# etna-sch-pmic.net
KiCad netlist of a schematic drawn in Altium Designer
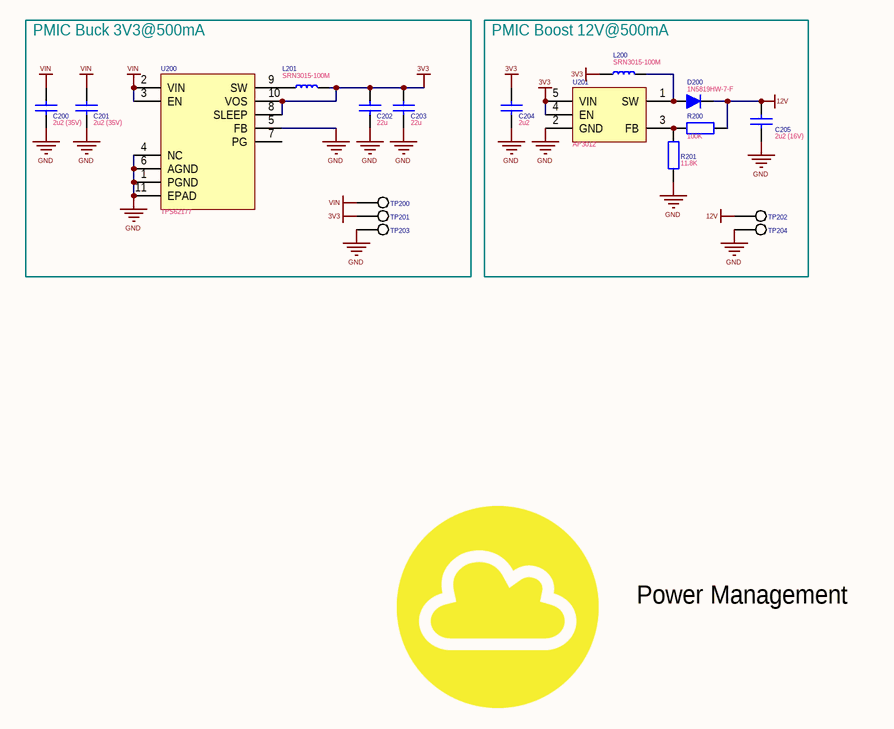
[diagram p0: etna-sch-pmic.SchDoc]

(export (version "E")
  (design (tool "Eeschema 10.0.6"))
  (components
    (comp (ref "C200")
      (value "2u2 (35V)")
      (footprint "0805-CAP")
      (description "Capacitor")
      (libsource (lib "illysky-components") (part "CAP"))
    )
    (comp (ref "C201")
      (value "2u2 (35V)")
      (footprint "0805-CAP")
      (description "Capacitor")
      (libsource (lib "illysky-components") (part "CAP"))
    )
    (comp (ref "C202")
      (value "22u")
      (footprint "0805-CAP")
      (description "Capacitor")
      (libsource (lib "illysky-components") (part "CAP"))
    )
    (comp (ref "C203")
      (value "22u")
      (footprint "0805-CAP")
      (description "Capacitor")
      (libsource (lib "illysky-components") (part "CAP"))
    )
    (comp (ref "C204")
      (value "2u2")
      (footprint "0603-capacitor")
      (description "Capacitor")
      (libsource (lib "illysky-components") (part "CAP"))
    )
    (comp (ref "C205")
      (value "2u2 (16V)")
      (footprint "0603-capacitor")
      (description "Capacitor")
      (libsource (lib "illysky-components") (part "CAP"))
    )
    (comp (ref "D200")
      (value "1N5819HW-7-F")
      (footprint "SOD123-DIODE")
      (description "Diode")
      (fields (field (name "PUBLISHER") "Altium Limited"))
      (libsource (lib "illysky-components") (part "DIODE"))
    )
    (comp (ref "L200")
      (value "SRN3015-100M")
      (footprint "SRN3015")
      (description "Inductor or Ferrite")
      (libsource (lib "illysky-components") (part "IND"))
    )
    (comp (ref "L201")
      (value "SRN3015-100M")
      (footprint "SRN3015")
      (description "Inductor or Ferrite")
      (libsource (lib "illysky-components") (part "IND"))
    )
    (comp (ref "R200")
      (value "100K")
      (footprint "0402-resistor")
      (description "Resistor")
      (libsource (lib "altium-import") (part "root_0_RES_"))
    )
    (comp (ref "R201")
      (value "11.8K")
      (footprint "0402-resistor")
      (description "Resistor")
      (libsource (lib "altium-import") (part "root_3_RES_"))
    )
    (comp (ref "TP200")
      (value "TP")
      (footprint "TESTPOINT")
      (libsource (lib "illysky-components") (part "TEST_POINT"))
    )
    (comp (ref "TP201")
      (value "TP")
      (footprint "TESTPOINT")
      (libsource (lib "illysky-components") (part "TEST_POINT"))
    )
    (comp (ref "TP202")
      (value "TP")
      (footprint "TESTPOINT")
      (libsource (lib "illysky-components") (part "TEST_POINT"))
    )
    (comp (ref "TP203")
      (value "TP")
      (footprint "TESTPOINT")
      (libsource (lib "illysky-components") (part "TEST_POINT"))
    )
    (comp (ref "TP204")
      (value "TP")
      (footprint "TESTPOINT")
      (libsource (lib "illysky-components") (part "TEST_POINT"))
    )
    (comp (ref "U200")
      (value "TPS62177")
      (footprint "WSON10")
      (description "TPS6217x 28-V, 0.5-A Step-Down Converter With Sleep Mode")
      (libsource (lib "illysky-components") (part "TPS62175"))
    )
    (comp (ref "U201")
      (value "AP3012")
      (footprint "SOT-235")
      (description "1.5MHz STEP-UP DC-DC CONVERTER")
      (libsource (lib "illysky-components") (part "AP3012"))
    )
  )
  (nets
    (net (code "1") (name "3V3") (class "Default")
      (node (ref "C202") (pin "2") (pinfunction "2_2") (pintype "passive"))
      (node (ref "C203") (pin "2") (pinfunction "2_2") (pintype "passive"))
      (node (ref "C204") (pin "2") (pinfunction "2_2") (pintype "passive"))
      (node (ref "L200") (pin "1") (pintype "passive"))
      (node (ref "L201") (pin "2") (pintype "passive"))
      (node (ref "TP201") (pin "1") (pinfunction "GND_1") (pintype "passive"))
      (node (ref "U200") (pin "10") (pinfunction "VOS_10") (pintype "passive"))
      (node (ref "U200") (pin "8") (pinfunction "SLEEP_8") (pintype "passive"))
      (node (ref "U201") (pin "4") (pinfunction "EN_4") (pintype "passive"))
      (node (ref "U201") (pin "5") (pinfunction "VIN_5") (pintype "passive"))
    )
    (net (code "2") (name "12V") (class "Default")
      (node (ref "C205") (pin "2") (pinfunction "2_2") (pintype "passive"))
      (node (ref "D200") (pin "2") (pinfunction "K_2") (pintype "passive"))
      (node (ref "R200") (pin "2") (pinfunction "2_2") (pintype "passive"))
      (node (ref "TP202") (pin "1") (pinfunction "GND_1") (pintype "passive"))
    )
    (net (code "3") (name "GND") (class "Default")
      (node (ref "C200") (pin "1") (pinfunction "1_1") (pintype "passive"))
      (node (ref "C201") (pin "1") (pinfunction "1_1") (pintype "passive"))
      (node (ref "C202") (pin "1") (pinfunction "1_1") (pintype "passive"))
      (node (ref "C203") (pin "1") (pinfunction "1_1") (pintype "passive"))
      (node (ref "C204") (pin "1") (pinfunction "1_1") (pintype "passive"))
      (node (ref "C205") (pin "1") (pinfunction "1_1") (pintype "passive"))
      (node (ref "R201") (pin "2") (pinfunction "2_2") (pintype "passive"))
      (node (ref "TP203") (pin "1") (pinfunction "GND_1") (pintype "passive"))
      (node (ref "TP204") (pin "1") (pinfunction "GND_1") (pintype "passive"))
      (node (ref "U200") (pin "1") (pinfunction "PGND_1") (pintype "passive"))
      (node (ref "U200") (pin "11") (pinfunction "EPAD_11") (pintype "passive"))
      (node (ref "U200") (pin "4") (pinfunction "NC_4") (pintype "passive"))
      (node (ref "U200") (pin "5") (pinfunction "FB_5") (pintype "passive"))
      (node (ref "U200") (pin "6") (pinfunction "AGND_6") (pintype "passive"))
      (node (ref "U201") (pin "2") (pinfunction "GND_2") (pintype "passive"))
    )
    (net (code "4") (name "Net-(D200-A)") (class "Default")
      (node (ref "D200") (pin "1") (pinfunction "A_1") (pintype "passive"))
      (node (ref "L200") (pin "2") (pintype "passive"))
      (node (ref "U201") (pin "1") (pinfunction "SW_1") (pintype "passive"))
    )
    (net (code "5") (name "Net-(U200-SW)") (class "Default")
      (node (ref "L201") (pin "1") (pintype "passive"))
      (node (ref "U200") (pin "9") (pinfunction "SW_9") (pintype "passive"))
    )
    (net (code "6") (name "Net-(U201-FB)") (class "Default")
      (node (ref "R200") (pin "1") (pinfunction "1_1") (pintype "passive"))
      (node (ref "R201") (pin "1") (pinfunction "1_1") (pintype "passive"))
      (node (ref "U201") (pin "3") (pinfunction "FB_3") (pintype "passive"))
    )
    (net (code "7") (name "VIN") (class "Default")
      (node (ref "C200") (pin "2") (pinfunction "2_2") (pintype "passive"))
      (node (ref "C201") (pin "2") (pinfunction "2_2") (pintype "passive"))
      (node (ref "TP200") (pin "1") (pinfunction "GND_1") (pintype "passive"))
      (node (ref "U200") (pin "2") (pinfunction "VIN_2") (pintype "passive"))
      (node (ref "U200") (pin "3") (pinfunction "EN_3") (pintype "passive"))
    )
    (net (code "8") (name "unconnected-(U200-PG-Pad7)") (class "Default")
      (node (ref "U200") (pin "7") (pinfunction "PG_7") (pintype "passive"))
    )
  )
)
